# EIP_PCB0_1.net
KiCad netlist of a schematic drawn in Altium Designer
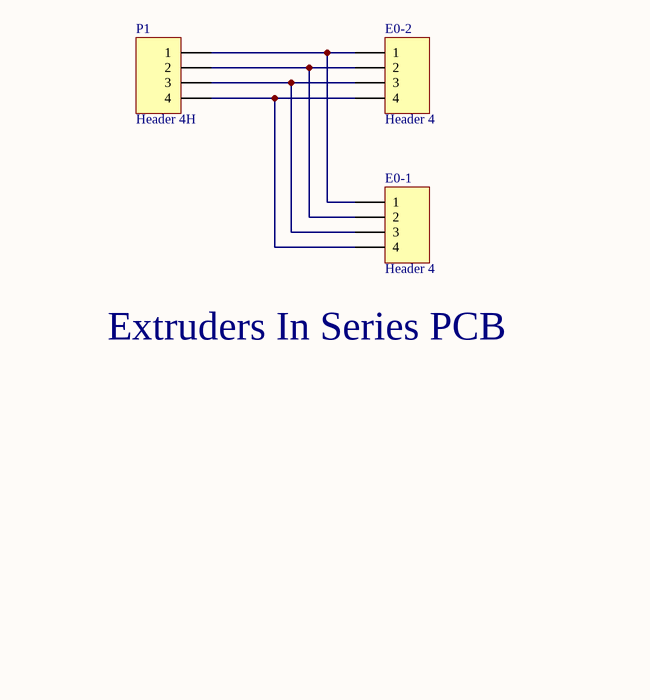
[diagram p0: EIP PCB0.1.SchDoc]

(export (version "E")
  (design (tool "Eeschema 10.0.6"))
  (components
    (comp (ref "E0-1")
      (value "Header 4")
      (footprint "HDR1X4")
      (description "CONN HEADER 4POS .100 VERT TIN")
      (fields (field (name "DIGI-KEY PART NUMBER") "WM4113-ND") (field (name "MANUFACTURER") "Molex, LLC"))
      (libsource (lib "SCH LIB") (part "Header 4"))
    )
    (comp (ref "E0-2")
      (value "Header 4")
      (footprint "HDR1X4")
      (description "CONN HEADER 4POS .100 VERT TIN")
      (fields (field (name "DIGI-KEY PART NUMBER") "WM4113-ND") (field (name "MANUFACTURER") "Molex, LLC"))
      (libsource (lib "SCH LIB") (part "Header 4"))
    )
    (comp (ref "P1")
      (value "Header 4H")
      (footprint "HDR1X4H")
      (description "CONN RECEPT 4POS .100 R/A PCB")
      (fields
        (field (name "DIGI-KEY PART NUMBER") "WM3002-ND")
        (field (name "MANUFACTURER PART NUMBER") "0022152046")
        (field (name "PUBLISHER") "Molex Connector Corporation")
      )
      (libsource (lib "SCH LIB") (part "Header 4H"))
    )
  )
  (nets
    (net (code "1") (name "Net-(E0-1-Pad1)") (class "Default")
      (node (ref "E0-1") (pin "1") (pinfunction "1_1") (pintype "passive"))
      (node (ref "E0-2") (pin "1") (pinfunction "1_1") (pintype "passive"))
      (node (ref "P1") (pin "1") (pinfunction "1_1") (pintype "passive"))
    )
    (net (code "2") (name "Net-(E0-1-Pad2)") (class "Default")
      (node (ref "E0-1") (pin "2") (pinfunction "2_2") (pintype "passive"))
      (node (ref "E0-2") (pin "2") (pinfunction "2_2") (pintype "passive"))
      (node (ref "P1") (pin "2") (pinfunction "2_2") (pintype "passive"))
    )
    (net (code "3") (name "Net-(E0-1-Pad3)") (class "Default")
      (node (ref "E0-1") (pin "3") (pinfunction "3_3") (pintype "passive"))
      (node (ref "E0-2") (pin "3") (pinfunction "3_3") (pintype "passive"))
      (node (ref "P1") (pin "3") (pinfunction "3_3") (pintype "passive"))
    )
    (net (code "4") (name "Net-(E0-1-Pad4)") (class "Default")
      (node (ref "E0-1") (pin "4") (pinfunction "4_4") (pintype "passive"))
      (node (ref "E0-2") (pin "4") (pinfunction "4_4") (pintype "passive"))
      (node (ref "P1") (pin "4") (pinfunction "4_4") (pintype "passive"))
    )
  )
)
